# KX1_DB.net
KiCad netlist of a schematic drawn in Altium Designer
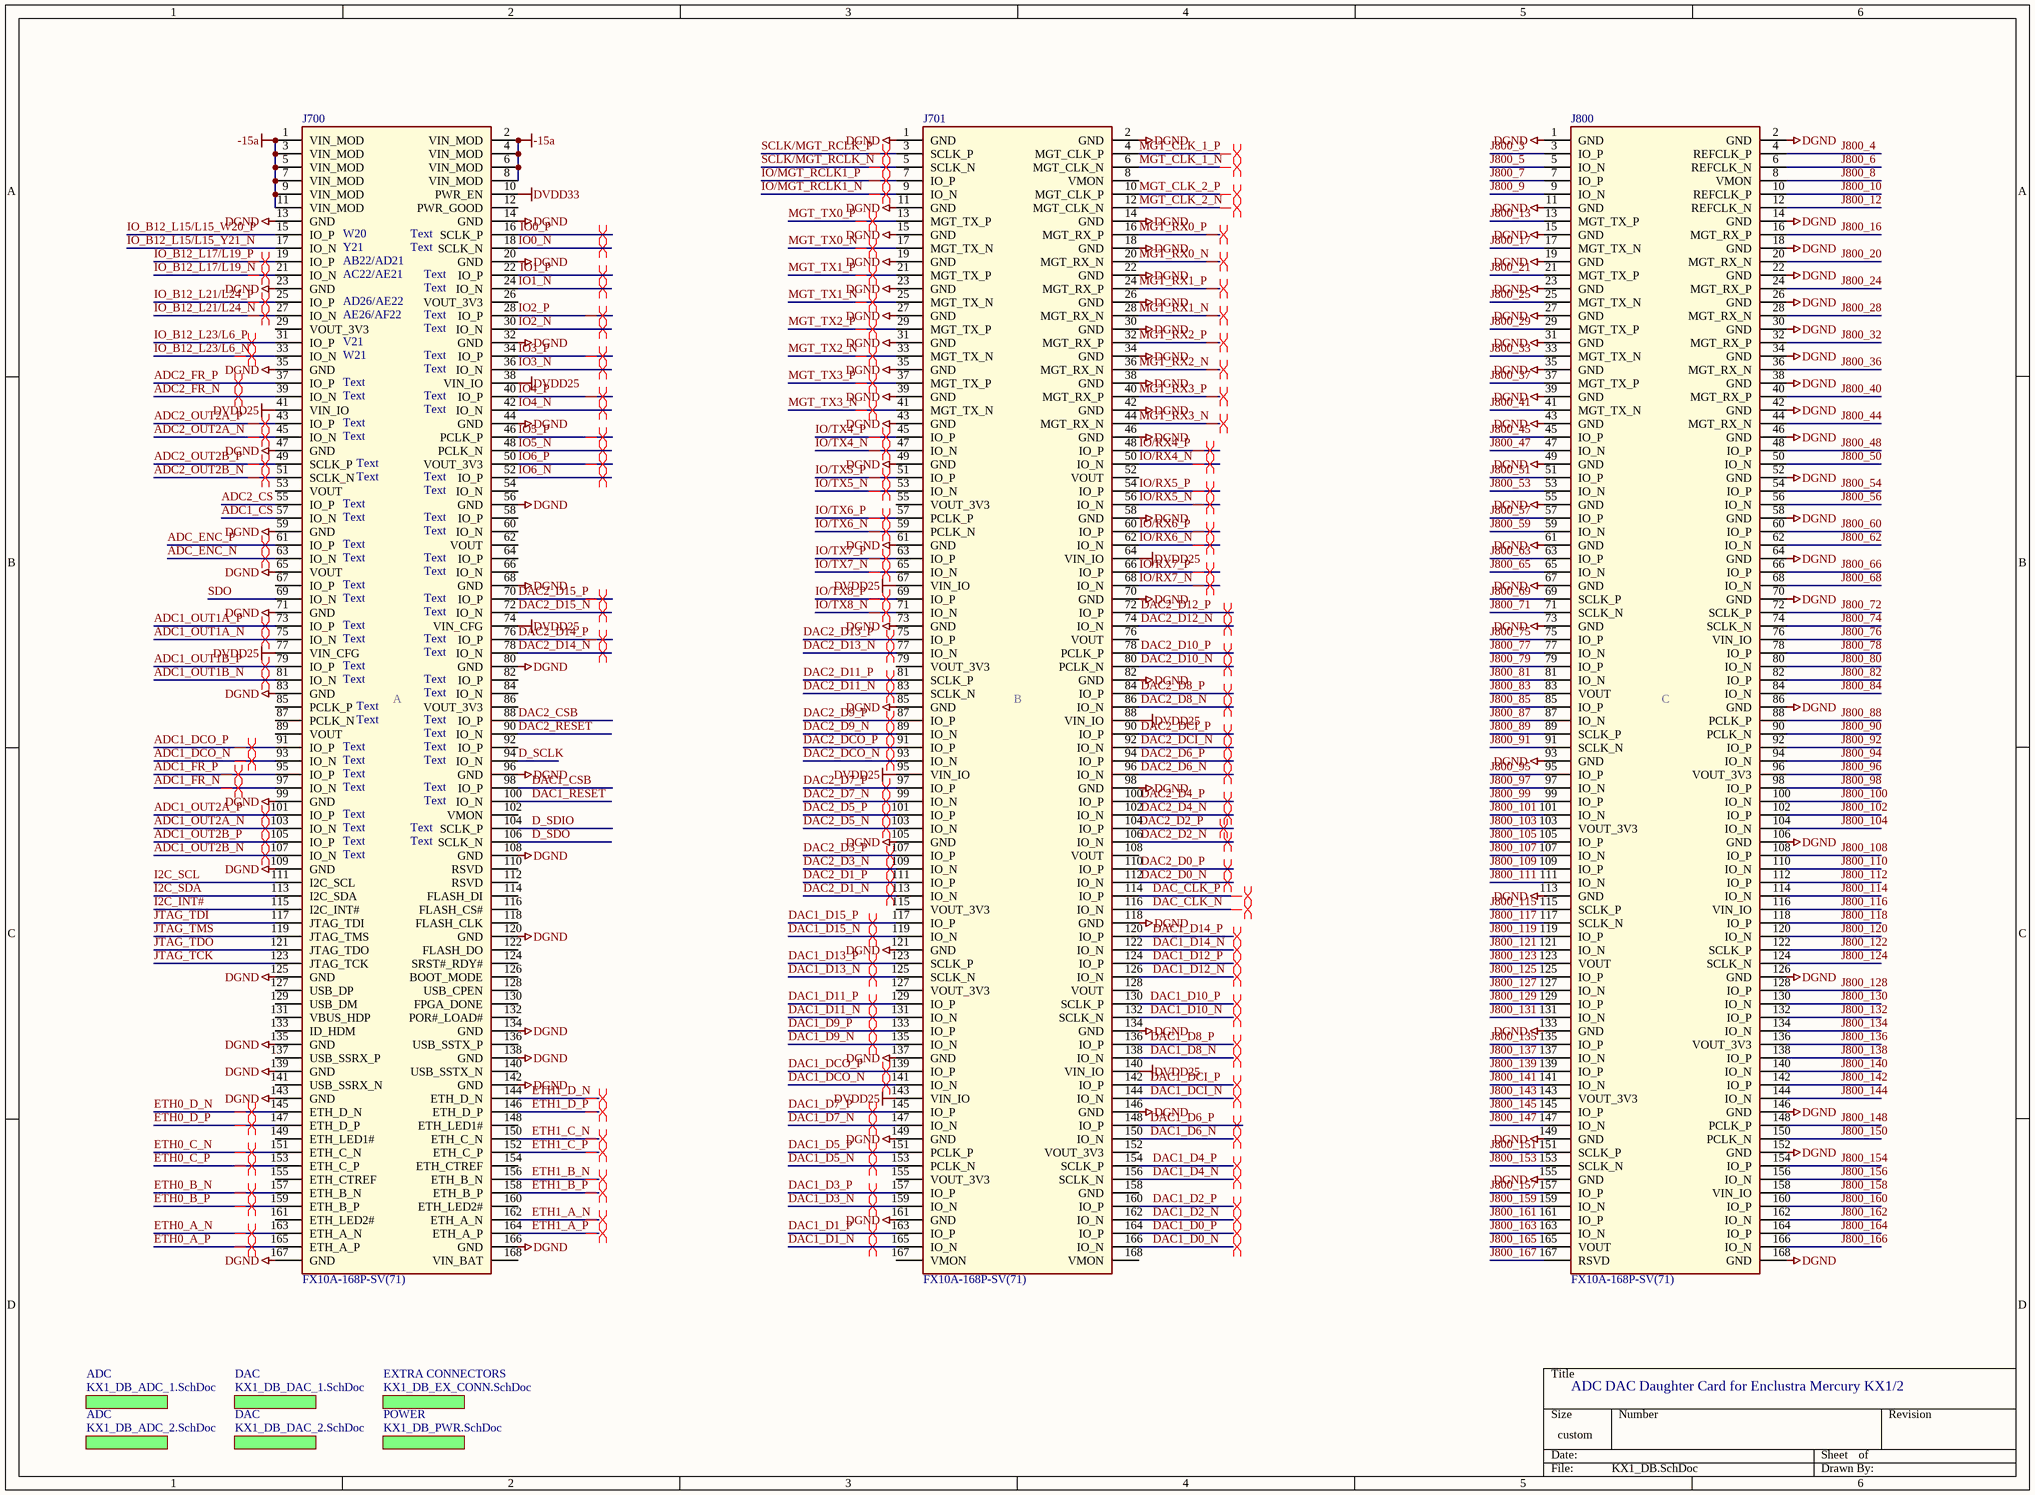
[diagram p0: KX1_DB.SchDoc]

(export (version "E")
  (design (tool "Eeschema 10.0.6"))
  (components
    (comp (ref "J700")
      (value "FX10A-168P-SV(71)")
      (footprint "Mercury_Baseboard_Connector")
      (description "Mercury Baseboard Connector")
      (fields
        (field (name "MANUFACTURER") "Hirose")
        (field (name "DISTPARTNUMBER") "FX10A-168P-SV(71)-ND")
        (field (name "CHECK SCH") "CG_2015-03-03")
      )
      (libsource (lib "Enclustra-Mars-Mercury-Altium-Library") (part "Mercury_Baseboard_Connector-A"))
    )
    (comp (ref "J701")
      (value "FX10A-168P-SV(71)")
      (footprint "Mercury_Baseboard_Connector")
      (description "Mercury Baseboard Connector")
      (fields
        (field (name "MANUFACTURER") "Hirose")
        (field (name "DISTPARTNUMBER") "FX10A-168P-SV(71)-ND")
        (field (name "CHECK SCH") "CG_2015-03-03")
      )
      (libsource (lib "Enclustra-Mars-Mercury-Altium-Library") (part "Mercury_Baseboard_Connector-B"))
    )
    (comp (ref "J800")
      (value "FX10A-168P-SV(71)")
      (footprint "Mercury_Baseboard_Connector")
      (description "Mercury Baseboard Connector")
      (fields
        (field (name "MANUFACTURER") "Hirose")
        (field (name "DISTPARTNUMBER") "FX10A-168P-SV(71)-ND")
        (field (name "CHECK SCH") "CG_2015-03-03")
      )
      (libsource (lib "Enclustra-Mars-Mercury-Altium-Library") (part "Mercury_Baseboard_Connector-C"))
    )
  )
  (nets
    (net (code "1") (name "-15a") (class "Default")
      (node (ref "J700") (pin "1") (pinfunction "VIN_MOD_1") (pintype "power_in"))
      (node (ref "J700") (pin "11") (pinfunction "VIN_MOD_11") (pintype "power_in"))
      (node (ref "J700") (pin "2") (pinfunction "VIN_MOD_2") (pintype "power_in"))
      (node (ref "J700") (pin "3") (pinfunction "VIN_MOD_3") (pintype "power_in"))
      (node (ref "J700") (pin "4") (pinfunction "VIN_MOD_4") (pintype "power_in"))
      (node (ref "J700") (pin "5") (pinfunction "VIN_MOD_5") (pintype "power_in"))
      (node (ref "J700") (pin "6") (pinfunction "VIN_MOD_6") (pintype "power_in"))
      (node (ref "J700") (pin "7") (pinfunction "VIN_MOD_7") (pintype "power_in"))
      (node (ref "J700") (pin "8") (pinfunction "VIN_MOD_8") (pintype "power_in"))
      (node (ref "J700") (pin "9") (pinfunction "VIN_MOD_9") (pintype "power_in"))
    )
    (net (code "2") (name "/ADC1_CS") (class "Default")
      (node (ref "J700") (pin "57") (pinfunction "IO_N_57") (pintype "passive"))
    )
    (net (code "3") (name "/ADC1_DCO_N") (class "Default")
      (node (ref "J700") (pin "93") (pinfunction "IO_N_93") (pintype "passive"))
    )
    (net (code "4") (name "/ADC1_DCO_P") (class "Default")
      (node (ref "J700") (pin "91") (pinfunction "IO_P_91") (pintype "passive"))
    )
    (net (code "5") (name "/ADC1_FR_N") (class "Default")
      (node (ref "J700") (pin "97") (pinfunction "IO_N_97") (pintype "passive"))
    )
    (net (code "6") (name "/ADC1_FR_P") (class "Default")
      (node (ref "J700") (pin "95") (pinfunction "IO_P_95") (pintype "passive"))
    )
    (net (code "7") (name "/ADC1_OUT1A_N") (class "Default")
      (node (ref "J700") (pin "75") (pinfunction "IO_N_75") (pintype "passive"))
    )
    (net (code "8") (name "/ADC1_OUT1A_P") (class "Default")
      (node (ref "J700") (pin "73") (pinfunction "IO_P_73") (pintype "passive"))
    )
    (net (code "9") (name "/ADC1_OUT1B_N") (class "Default")
      (node (ref "J700") (pin "81") (pinfunction "IO_N_81") (pintype "passive"))
    )
    (net (code "10") (name "/ADC1_OUT1B_P") (class "Default")
      (node (ref "J700") (pin "79") (pinfunction "IO_P_79") (pintype "passive"))
    )
    (net (code "11") (name "/ADC1_OUT2A_N") (class "Default")
      (node (ref "J700") (pin "103") (pinfunction "IO_N_103") (pintype "passive"))
    )
    (net (code "12") (name "/ADC1_OUT2A_P") (class "Default")
      (node (ref "J700") (pin "101") (pinfunction "IO_P_101") (pintype "passive"))
    )
    (net (code "13") (name "/ADC1_OUT2B_N") (class "Default")
      (node (ref "J700") (pin "107") (pinfunction "IO_N_107") (pintype "passive"))
    )
    (net (code "14") (name "/ADC1_OUT2B_P") (class "Default")
      (node (ref "J700") (pin "105") (pinfunction "IO_P_105") (pintype "passive"))
    )
    (net (code "15") (name "/ADC2_CS") (class "Default")
      (node (ref "J700") (pin "55") (pinfunction "IO_P_55") (pintype "passive"))
    )
    (net (code "16") (name "/ADC2_FR_N") (class "Default")
      (node (ref "J700") (pin "39") (pinfunction "IO_N_39") (pintype "passive"))
    )
    (net (code "17") (name "/ADC2_FR_P") (class "Default")
      (node (ref "J700") (pin "37") (pinfunction "IO_P_37") (pintype "passive"))
    )
    (net (code "18") (name "/ADC2_OUT2A_N") (class "Default")
      (node (ref "J700") (pin "45") (pinfunction "IO_N_45") (pintype "passive"))
    )
    (net (code "19") (name "/ADC2_OUT2A_P") (class "Default")
      (node (ref "J700") (pin "43") (pinfunction "IO_P_43") (pintype "passive"))
    )
    (net (code "20") (name "/ADC2_OUT2B_N") (class "Default")
      (node (ref "J700") (pin "51") (pinfunction "SCLK_N_51") (pintype "passive"))
    )
    (net (code "21") (name "/ADC2_OUT2B_P") (class "Default")
      (node (ref "J700") (pin "49") (pinfunction "SCLK_P_49") (pintype "passive"))
    )
    (net (code "22") (name "/ADC_ENC_N") (class "Default")
      (node (ref "J700") (pin "63") (pinfunction "IO_N_63") (pintype "passive"))
    )
    (net (code "23") (name "/ADC_ENC_P") (class "Default")
      (node (ref "J700") (pin "61") (pinfunction "IO_P_61") (pintype "passive"))
    )
    (net (code "24") (name "/DAC1_CSB") (class "Default")
      (node (ref "J700") (pin "98") (pinfunction "IO_P_98") (pintype "passive"))
    )
    (net (code "25") (name "/DAC1_D0_N") (class "Default")
      (node (ref "J701") (pin "166") (pinfunction "IO_N_166") (pintype "passive"))
    )
    (net (code "26") (name "/DAC1_D0_P") (class "Default")
      (node (ref "J701") (pin "164") (pinfunction "IO_P_164") (pintype "passive"))
    )
    (net (code "27") (name "/DAC1_D1_N") (class "Default")
      (node (ref "J701") (pin "165") (pinfunction "IO_N_165") (pintype "passive"))
    )
    (net (code "28") (name "/DAC1_D1_P") (class "Default")
      (node (ref "J701") (pin "163") (pinfunction "IO_P_163") (pintype "passive"))
    )
    (net (code "29") (name "/DAC1_D2_N") (class "Default")
      (node (ref "J701") (pin "162") (pinfunction "IO_N_162") (pintype "passive"))
    )
    (net (code "30") (name "/DAC1_D2_P") (class "Default")
      (node (ref "J701") (pin "160") (pinfunction "IO_P_160") (pintype "passive"))
    )
    (net (code "31") (name "/DAC1_D3_N") (class "Default")
      (node (ref "J701") (pin "159") (pinfunction "IO_N_159") (pintype "passive"))
    )
    (net (code "32") (name "/DAC1_D3_P") (class "Default")
      (node (ref "J701") (pin "157") (pinfunction "IO_P_157") (pintype "passive"))
    )
    (net (code "33") (name "/DAC1_D4_N") (class "Default")
      (node (ref "J701") (pin "156") (pinfunction "SCLK_N_156") (pintype "passive"))
    )
    (net (code "34") (name "/DAC1_D4_P") (class "Default")
      (node (ref "J701") (pin "154") (pinfunction "SCLK_P_154") (pintype "passive"))
    )
    (net (code "35") (name "/DAC1_D5_N") (class "Default")
      (node (ref "J701") (pin "153") (pinfunction "PCLK_N_153") (pintype "passive"))
    )
    (net (code "36") (name "/DAC1_D5_P") (class "Default")
      (node (ref "J701") (pin "151") (pinfunction "PCLK_P_151") (pintype "passive"))
    )
    (net (code "37") (name "/DAC1_D6_N") (class "Default")
      (node (ref "J701") (pin "150") (pinfunction "IO_N_150") (pintype "passive"))
    )
    (net (code "38") (name "/DAC1_D6_P") (class "Default")
      (node (ref "J701") (pin "148") (pinfunction "IO_P_148") (pintype "passive"))
    )
    (net (code "39") (name "/DAC1_D7_N") (class "Default")
      (node (ref "J701") (pin "147") (pinfunction "IO_N_147") (pintype "passive"))
    )
    (net (code "40") (name "/DAC1_D7_P") (class "Default")
      (node (ref "J701") (pin "145") (pinfunction "IO_P_145") (pintype "passive"))
    )
    (net (code "41") (name "/DAC1_D8_N") (class "Default")
      (node (ref "J701") (pin "138") (pinfunction "IO_N_138") (pintype "passive"))
    )
    (net (code "42") (name "/DAC1_D8_P") (class "Default")
      (node (ref "J701") (pin "136") (pinfunction "IO_P_136") (pintype "passive"))
    )
    (net (code "43") (name "/DAC1_D9_N") (class "Default")
      (node (ref "J701") (pin "135") (pinfunction "IO_N_135") (pintype "passive"))
    )
    (net (code "44") (name "/DAC1_D9_P") (class "Default")
      (node (ref "J701") (pin "133") (pinfunction "IO_P_133") (pintype "passive"))
    )
    (net (code "45") (name "/DAC1_D10_N") (class "Default")
      (node (ref "J701") (pin "132") (pinfunction "SCLK_N_132") (pintype "passive"))
    )
    (net (code "46") (name "/DAC1_D10_P") (class "Default")
      (node (ref "J701") (pin "130") (pinfunction "SCLK_P_130") (pintype "passive"))
    )
    (net (code "47") (name "/DAC1_D11_N") (class "Default")
      (node (ref "J701") (pin "131") (pinfunction "IO_N_131") (pintype "passive"))
    )
    (net (code "48") (name "/DAC1_D11_P") (class "Default")
      (node (ref "J701") (pin "129") (pinfunction "IO_P_129") (pintype "passive"))
    )
    (net (code "49") (name "/DAC1_D12_N") (class "Default")
      (node (ref "J701") (pin "126") (pinfunction "IO_N_126") (pintype "passive"))
    )
    (net (code "50") (name "/DAC1_D12_P") (class "Default")
      (node (ref "J701") (pin "124") (pinfunction "IO_P_124") (pintype "passive"))
    )
    (net (code "51") (name "/DAC1_D13_N") (class "Default")
      (node (ref "J701") (pin "125") (pinfunction "SCLK_N_125") (pintype "passive"))
    )
    (net (code "52") (name "/DAC1_D13_P") (class "Default")
      (node (ref "J701") (pin "123") (pinfunction "SCLK_P_123") (pintype "passive"))
    )
    (net (code "53") (name "/DAC1_D14_N") (class "Default")
      (node (ref "J701") (pin "122") (pinfunction "IO_N_122") (pintype "passive"))
    )
    (net (code "54") (name "/DAC1_D14_P") (class "Default")
      (node (ref "J701") (pin "120") (pinfunction "IO_P_120") (pintype "passive"))
    )
    (net (code "55") (name "/DAC1_D15_N") (class "Default")
      (node (ref "J701") (pin "119") (pinfunction "IO_N_119") (pintype "passive"))
    )
    (net (code "56") (name "/DAC1_D15_P") (class "Default")
      (node (ref "J701") (pin "117") (pinfunction "IO_P_117") (pintype "passive"))
    )
    (net (code "57") (name "/DAC1_DCI_N") (class "Default")
      (node (ref "J701") (pin "144") (pinfunction "IO_N_144") (pintype "passive"))
    )
    (net (code "58") (name "/DAC1_DCI_P") (class "Default")
      (node (ref "J701") (pin "142") (pinfunction "IO_P_142") (pintype "passive"))
    )
    (net (code "59") (name "/DAC1_DCO_N") (class "Default")
      (node (ref "J701") (pin "141") (pinfunction "IO_N_141") (pintype "passive"))
    )
    (net (code "60") (name "/DAC1_DCO_P") (class "Default")
      (node (ref "J701") (pin "139") (pinfunction "IO_P_139") (pintype "passive"))
    )
    (net (code "61") (name "/DAC1_RESET") (class "Default")
      (node (ref "J700") (pin "100") (pinfunction "IO_N_100") (pintype "passive"))
    )
    (net (code "62") (name "/DAC2_CSB") (class "Default")
      (node (ref "J700") (pin "88") (pinfunction "IO_P_88") (pintype "passive"))
    )
    (net (code "63") (name "/DAC2_D0_N") (class "Default")
      (node (ref "J701") (pin "112") (pinfunction "IO_N_112") (pintype "passive"))
    )
    (net (code "64") (name "/DAC2_D0_P") (class "Default")
      (node (ref "J701") (pin "110") (pinfunction "IO_P_110") (pintype "passive"))
    )
    (net (code "65") (name "/DAC2_D1_N") (class "Default")
      (node (ref "J701") (pin "113") (pinfunction "IO_N_113") (pintype "passive"))
    )
    (net (code "66") (name "/DAC2_D1_P") (class "Default")
      (node (ref "J701") (pin "111") (pinfunction "IO_P_111") (pintype "passive"))
    )
    (net (code "67") (name "/DAC2_D2_N") (class "Default")
      (node (ref "J701") (pin "106") (pinfunction "IO_N_106") (pintype "passive"))
    )
    (net (code "68") (name "/DAC2_D2_P") (class "Default")
      (node (ref "J701") (pin "104") (pinfunction "IO_P_104") (pintype "passive"))
    )
    (net (code "69") (name "/DAC2_D3_N") (class "Default")
      (node (ref "J701") (pin "109") (pinfunction "IO_N_109") (pintype "passive"))
    )
    (net (code "70") (name "/DAC2_D3_P") (class "Default")
      (node (ref "J701") (pin "107") (pinfunction "IO_P_107") (pintype "passive"))
    )
    (net (code "71") (name "/DAC2_D4_N") (class "Default")
      (node (ref "J701") (pin "102") (pinfunction "IO_N_102") (pintype "passive"))
    )
    (net (code "72") (name "/DAC2_D4_P") (class "Default")
      (node (ref "J701") (pin "100") (pinfunction "IO_P_100") (pintype "passive"))
    )
    (net (code "73") (name "/DAC2_D5_N") (class "Default")
      (node (ref "J701") (pin "103") (pinfunction "IO_N_103") (pintype "passive"))
    )
    (net (code "74") (name "/DAC2_D5_P") (class "Default")
      (node (ref "J701") (pin "101") (pinfunction "IO_P_101") (pintype "passive"))
    )
    (net (code "75") (name "/DAC2_D6_N") (class "Default")
      (node (ref "J701") (pin "96") (pinfunction "IO_N_96") (pintype "passive"))
    )
    (net (code "76") (name "/DAC2_D6_P") (class "Default")
      (node (ref "J701") (pin "94") (pinfunction "IO_P_94") (pintype "passive"))
    )
    (net (code "77") (name "/DAC2_D7_N") (class "Default")
      (node (ref "J701") (pin "99") (pinfunction "IO_N_99") (pintype "passive"))
    )
    (net (code "78") (name "/DAC2_D7_P") (class "Default")
      (node (ref "J701") (pin "97") (pinfunction "IO_P_97") (pintype "passive"))
    )
    (net (code "79") (name "/DAC2_D8_N") (class "Default")
      (node (ref "J701") (pin "86") (pinfunction "IO_N_86") (pintype "passive"))
    )
    (net (code "80") (name "/DAC2_D8_P") (class "Default")
      (node (ref "J701") (pin "84") (pinfunction "IO_P_84") (pintype "passive"))
    )
    (net (code "81") (name "/DAC2_D9_N") (class "Default")
      (node (ref "J701") (pin "89") (pinfunction "IO_N_89") (pintype "passive"))
    )
    (net (code "82") (name "/DAC2_D9_P") (class "Default")
      (node (ref "J701") (pin "87") (pinfunction "IO_P_87") (pintype "passive"))
    )
    (net (code "83") (name "/DAC2_D10_N") (class "Default")
      (node (ref "J701") (pin "80") (pinfunction "PCLK_N_80") (pintype "passive"))
    )
    (net (code "84") (name "/DAC2_D10_P") (class "Default")
      (node (ref "J701") (pin "78") (pinfunction "PCLK_P_78") (pintype "passive"))
    )
    (net (code "85") (name "/DAC2_D11_N") (class "Default")
      (node (ref "J701") (pin "83") (pinfunction "SCLK_N_83") (pintype "passive"))
    )
    (net (code "86") (name "/DAC2_D11_P") (class "Default")
      (node (ref "J701") (pin "81") (pinfunction "SCLK_P_81") (pintype "passive"))
    )
    (net (code "87") (name "/DAC2_D12_N") (class "Default")
      (node (ref "J701") (pin "74") (pinfunction "IO_N_74") (pintype "passive"))
    )
    (net (code "88") (name "/DAC2_D12_P") (class "Default")
      (node (ref "J701") (pin "72") (pinfunction "IO_P_72") (pintype "passive"))
    )
    (net (code "89") (name "/DAC2_D13_N") (class "Default")
      (node (ref "J701") (pin "77") (pinfunction "IO_N_77") (pintype "passive"))
    )
    (net (code "90") (name "/DAC2_D13_P") (class "Default")
      (node (ref "J701") (pin "75") (pinfunction "IO_P_75") (pintype "passive"))
    )
    (net (code "91") (name "/DAC2_D14_N") (class "Default")
      (node (ref "J700") (pin "78") (pinfunction "IO_N_78") (pintype "passive"))
    )
    (net (code "92") (name "/DAC2_D14_P") (class "Default")
      (node (ref "J700") (pin "76") (pinfunction "IO_P_76") (pintype "passive"))
    )
    (net (code "93") (name "/DAC2_D15_N") (class "Default")
      (node (ref "J700") (pin "72") (pinfunction "IO_N_72") (pintype "passive"))
    )
    (net (code "94") (name "/DAC2_D15_P") (class "Default")
      (node (ref "J700") (pin "70") (pinfunction "IO_P_70") (pintype "passive"))
    )
    (net (code "95") (name "/DAC2_DCI_N") (class "Default")
      (node (ref "J701") (pin "92") (pinfunction "IO_N_92") (pintype "passive"))
    )
    (net (code "96") (name "/DAC2_DCI_P") (class "Default")
      (node (ref "J701") (pin "90") (pinfunction "IO_P_90") (pintype "passive"))
    )
    (net (code "97") (name "/DAC2_DCO_N") (class "Default")
      (node (ref "J701") (pin "93") (pinfunction "IO_N_93") (pintype "passive"))
    )
    (net (code "98") (name "/DAC2_DCO_P") (class "Default")
      (node (ref "J701") (pin "91") (pinfunction "IO_P_91") (pintype "passive"))
    )
    (net (code "99") (name "/DAC2_RESET") (class "Default")
      (node (ref "J700") (pin "90") (pinfunction "IO_N_90") (pintype "passive"))
    )
    (net (code "100") (name "/DAC_CLK_N") (class "Default")
      (node (ref "J701") (pin "116") (pinfunction "IO_N_116") (pintype "passive"))
    )
    (net (code "101") (name "/DAC_CLK_P") (class "Default")
      (node (ref "J701") (pin "114") (pinfunction "IO_P_114") (pintype "passive"))
    )
    (net (code "102") (name "/D_SCLK") (class "Default")
      (node (ref "J700") (pin "94") (pinfunction "IO_N_94") (pintype "passive"))
    )
    (net (code "103") (name "/D_SDIO") (class "Default")
      (node (ref "J700") (pin "104") (pinfunction "SCLK_P_104") (pintype "passive"))
    )
    (net (code "104") (name "/D_SDO") (class "Default")
      (node (ref "J700") (pin "106") (pinfunction "SCLK_N_106") (pintype "passive"))
    )
    (net (code "105") (name "/ETH0_A_N") (class "Default")
      (node (ref "J700") (pin "163") (pinfunction "ETH_A_N_163") (pintype "passive"))
    )
    (net (code "106") (name "/ETH0_A_P") (class "Default")
      (node (ref "J700") (pin "165") (pinfunction "ETH_A_P_165") (pintype "passive"))
    )
    (net (code "107") (name "/ETH0_B_N") (class "Default")
      (node (ref "J700") (pin "157") (pinfunction "ETH_B_N_157") (pintype "passive"))
    )
    (net (code "108") (name "/ETH0_B_P") (class "Default")
      (node (ref "J700") (pin "159") (pinfunction "ETH_B_P_159") (pintype "passive"))
    )
    (net (code "109") (name "/ETH0_C_N") (class "Default")
      (node (ref "J700") (pin "151") (pinfunction "ETH_C_N_151") (pintype "passive"))
    )
    (net (code "110") (name "/ETH0_C_P") (class "Default")
      (node (ref "J700") (pin "153") (pinfunction "ETH_C_P_153") (pintype "passive"))
    )
    (net (code "111") (name "/ETH0_D_N") (class "Default")
      (node (ref "J700") (pin "145") (pinfunction "ETH_D_N_145") (pintype "passive"))
    )
    (net (code "112") (name "/ETH0_D_P") (class "Default")
      (node (ref "J700") (pin "147") (pinfunction "ETH_D_P_147") (pintype "passive"))
    )
    (net (code "113") (name "/ETH1_A_N") (class "Default")
      (node (ref "J700") (pin "162") (pinfunction "ETH_A_N_162") (pintype "passive"))
    )
    (net (code "114") (name "/ETH1_A_P") (class "Default")
      (node (ref "J700") (pin "164") (pinfunction "ETH_A_P_164") (pintype "passive"))
    )
    (net (code "115") (name "/ETH1_B_N") (class "Default")
      (node (ref "J700") (pin "156") (pinfunction "ETH_B_N_156") (pintype "passive"))
    )
    (net (code "116") (name "/ETH1_B_P") (class "Default")
      (node (ref "J700") (pin "158") (pinfunction "ETH_B_P_158") (pintype "passive"))
    )
    (net (code "117") (name "/ETH1_C_N") (class "Default")
      (node (ref "J700") (pin "150") (pinfunction "ETH_C_N_150") (pintype "passive"))
    )
    (net (code "118") (name "/ETH1_C_P") (class "Default")
      (node (ref "J700") (pin "152") (pinfunction "ETH_C_P_152") (pintype "passive"))
    )
    (net (code "119") (name "/ETH1_D_N") (class "Default")
      (node (ref "J700") (pin "144") (pinfunction "ETH_D_N_144") (pintype "passive"))
    )
    (net (code "120") (name "/ETH1_D_P") (class "Default")
      (node (ref "J700") (pin "146") (pinfunction "ETH_D_P_146") (pintype "passive"))
    )
    (net (code "121") (name "/I2C_INT#") (class "Default")
      (node (ref "J700") (pin "115") (pinfunction "I2C_INT#_115") (pintype "passive"))
    )
    (net (code "122") (name "/I2C_SCL") (class "Default")
      (node (ref "J700") (pin "111") (pinfunction "I2C_SCL_111") (pintype "passive"))
    )
    (net (code "123") (name "/I2C_SDA") (class "Default")
      (node (ref "J700") (pin "113") (pinfunction "I2C_SDA_113") (pintype "passive"))
    )
    (net (code "124") (name "/IO0_N") (class "Default")
      (node (ref "J700") (pin "18") (pinfunction "SCLK_N_18") (pintype "passive"))
    )
    (net (code "125") (name "/IO0_P") (class "Default")
      (node (ref "J700") (pin "16") (pinfunction "SCLK_P_16") (pintype "passive"))
    )
    (net (code "126") (name "/IO1_N") (class "Default")
      (node (ref "J700") (pin "24") (pinfunction "IO_N_24") (pintype "passive"))
    )
    (net (code "127") (name "/IO1_P") (class "Default")
      (node (ref "J700") (pin "22") (pinfunction "IO_P_22") (pintype "passive"))
    )
    (net (code "128") (name "/IO2_N") (class "Default")
      (node (ref "J700") (pin "30") (pinfunction "IO_N_30") (pintype "passive"))
    )
    (net (code "129") (name "/IO2_P") (class "Default")
      (node (ref "J700") (pin "28") (pinfunction "IO_P_28") (pintype "passive"))
    )
    (net (code "130") (name "/IO3_N") (class "Default")
      (node (ref "J700") (pin "36") (pinfunction "IO_N_36") (pintype "passive"))
    )
    (net (code "131") (name "/IO3_P") (class "Default")
      (node (ref "J700") (pin "34") (pinfunction "IO_P_34") (pintype "passive"))
    )
    (net (code "132") (name "/IO4_N") (class "Default")
      (node (ref "J700") (pin "42") (pinfunction "IO_N_42") (pintype "passive"))
    )
    (net (code "133") (name "/IO4_P") (class "Default")
      (node (ref "J700") (pin "40") (pinfunction "IO_P_40") (pintype "passive"))
    )
    (net (code "134") (name "/IO5_N") (class "Default")
      (node (ref "J700") (pin "48") (pinfunction "PCLK_N_48") (pintype "passive"))
    )
    (net (code "135") (name "/IO5_P") (class "Default")
      (node (ref "J700") (pin "46") (pinfunction "PCLK_P_46") (pintype "passive"))
    )
    (net (code "136") (name "/IO6_N") (class "Default")
      (node (ref "J700") (pin "52") (pinfunction "IO_P_52") (pintype "passive"))
    )
    (net (code "137") (name "/IO6_P") (class "Default")
      (node (ref "J700") (pin "50") (pinfunction "VOUT_3V3_50") (pintype "power_in"))
    )
    (net (code "138") (name "/IO_B12_L15{slash}L15_W20_P") (class "Default")
      (node (ref "J700") (pin "15") (pinfunction "IO_P_15") (pintype "passive"))
    )
    (net (code "139") (name "/IO_B12_L15{slash}L15_Y21_N") (class "Default")
      (node (ref "J700") (pin "17") (pinfunction "IO_N_17") (pintype "passive"))
    )
    (net (code "140") (name "/IO_B12_L17{slash}L19_N") (class "Default")
      (node (ref "J700") (pin "21") (pinfunction "IO_N_21") (pintype "passive"))
    )
    (net (code "141") (name "/IO_B12_L17{slash}L19_P") (class "Default")
      (node (ref "J700") (pin "19") (pinfunction "IO_P_19") (pintype "passive"))
    )
    (net (code "142") (name "/IO_B12_L21{slash}L24_N") (class "Default")
      (node (ref "J700") (pin "27") (pinfunction "IO_N_27") (pintype "passive"))
    )
    (net (code "143") (name "/IO_B12_L21{slash}L24_P") (class "Default")
      (node (ref "J700") (pin "25") (pinfunction "IO_P_25") (pintype "passive"))
    )
    (net (code "144") (name "/IO_B12_L23{slash}L6_N") (class "Default")
      (node (ref "J700") (pin "33") (pinfunction "IO_N_33") (pintype "passive"))
    )
    (net (code "145") (name "/IO_B12_L23{slash}L6_P") (class "Default")
      (node (ref "J700") (pin "31") (pinfunction "IO_P_31") (pintype "passive"))
    )
    (net (code "146") (name "/IO{slash}MGT_RCLK1_N") (class "Default")
      (node (ref "J701") (pin "9") (pinfunction "IO_N_9") (pintype "passive"))
    )
    (net (code "147") (name "/IO{slash}MGT_RCLK1_P") (class "Default")
      (node (ref "J701") (pin "7") (pinfunction "IO_P_7") (pintype "passive"))
    )
    (net (code "148") (name "/IO{slash}RX4_N") (class "Default")
      (node (ref "J701") (pin "50") (pinfunction "IO_N_50") (pintype "passive"))
    )
    (net (code "149") (name "/IO{slash}RX4_P") (class "Default")
      (node (ref "J701") (pin "48") (pinfunction "IO_P_48") (pintype "passive"))
    )
    (net (code "150") (name "/IO{slash}RX5_N") (class "Default")
      (node (ref "J701") (pin "56") (pinfunction "IO_N_56") (pintype "passive"))
    )
    (net (code "151") (name "/IO{slash}RX5_P") (class "Default")
      (node (ref "J701") (pin "54") (pinfunction "IO_P_54") (pintype "passive"))
    )
    (net (code "152") (name "/IO{slash}RX6_N") (class "Default")
      (node (ref "J701") (pin "62") (pinfunction "IO_N_62") (pintype "passive"))
    )
    (net (code "153") (name "/IO{slash}RX6_P") (class "Default")
      (node (ref "J701") (pin "60") (pinfunction "IO_P_60") (pintype "passive"))
    )
    (net (code "154") (name "/IO{slash}RX7_N") (class "Default")
      (node (ref "J701") (pin "68") (pinfunction "IO_N_68") (pintype "passive"))
    )
    (net (code "155") (name "/IO{slash}RX7_P") (class "Default")
      (node (ref "J701") (pin "66") (pinfunction "IO_P_66") (pintype "passive"))
    )
    (net (code "156") (name "/IO{slash}TX4_N") (class "Default")
      (node (ref "J701") (pin "47") (pinfunction "IO_N_47") (pintype "passive"))
    )
    (net (code "157") (name "/IO{slash}TX4_P") (class "Default")
      (node (ref "J701") (pin "45") (pinfunction "IO_P_45") (pintype "passive"))
    )
    (net (code "158") (name "/IO{slash}TX5_N") (class "Default")
      (node (ref "J701") (pin "53") (pinfunction "IO_N_53") (pintype "passive"))
    )
    (net (code "159") (name "/IO{slash}TX5_P") (class "Default")
      (node (ref "J701") (pin "51") (pinfunction "IO_P_51") (pintype "passive"))
    )
    (net (code "160") (name "/IO{slash}TX6_N") (class "Default")
      (node (ref "J701") (pin "59") (pinfunction "PCLK_N_59") (pintype "passive"))
    )
    (net (code "161") (name "/IO{slash}TX6_P") (class "Default")
      (node (ref "J701") (pin "57") (pinfunction "PCLK_P_57") (pintype "passive"))
    )
    (net (code "162") (name "/IO{slash}TX7_N") (class "Default")
      (node (ref "J701") (pin "65") (pinfunction "IO_N_65") (pintype "passive"))
    )
    (net (code "163") (name "/IO{slash}TX7_P") (class "Default")
      (node (ref "J701") (pin "63") (pinfunction "IO_P_63") (pintype "passive"))
    )
    (net (code "164") (name "/IO{slash}TX8_N") (class "Default")
      (node (ref "J701") (pin "71") (pinfunction "IO_N_71") (pintype "passive"))
    )
    (net (code "165") (name "/IO{slash}TX8_P") (class "Default")
      (node (ref "J701") (pin "69") (pinfunction "IO_P_69") (pintype "passive"))
    )
    (net (code "166") (name "/J800_3") (class "Default")
      (node (ref "J800") (pin "3") (pinfunction "IO_P_3") (pintype "passive"))
    )
    (net (code "167") (name "/J800_4") (class "Default")
      (node (ref "J800") (pin "4") (pinfunction "REFCLK_P_4") (pintype "passive"))
    )
    (net (code "168") (name "/J800_5") (class "Default")
      (node (ref "J800") (pin "5") (pinfunction "IO_N_5") (pintype "passive"))
    )
    (net (code "169") (name "/J800_6") (class "Default")
      (node (ref "J800") (pin "6") (pinfunction "REFCLK_N_6") (pintype "passive"))
    )
    (net (code "170") (name "/J800_7") (class "Default")
      (node (ref "J800") (pin "7") (pinfunction "IO_P_7") (pintype "passive"))
    )
    (net (code "171") (name "/J800_8") (class "Default")
      (node (ref "J800") (pin "8") (pinfunction "VMON_8") (pintype "passive"))
    )
    (net (code "172") (name "/J800_9") (class "Default")
      (node (ref "J800") (pin "9") (pinfunction "IO_N_9") (pintype "passive"))
    )
    (net (code "173") (name "/J800_10") (class "Default")
      (node (ref "J800") (pin "10") (pinfunction "REFCLK_P_10") (pintype "passive"))
    )
    (net (code "174") (name "/J800_12") (class "Default")
      (node (ref "J800") (pin "12") (pinfunction "REFCLK_N_12") (pintype "passive"))
    )
    (net (code "175") (name "/J800_13") (class "Default")
      (node (ref "J800") (pin "13") (pinfunction "MGT_TX_P_13") (pintype "passive"))
    )
    (net (code "176") (name "/J800_16") (class "Default")
      (node (ref "J800") (pin "16") (pinfunction "MGT_RX_P_16") (pintype "passive"))
    )
    (net (code "177") (name "/J800_17") (class "Default")
      (node (ref "J800") (pin "17") (pinfunction "MGT_TX_N_17") (pintype "passive"))
    )
    (net (code "178") (name "/J800_20") (class "Default")
      (node (ref "J800") (pin "20") (pinfunction "MGT_RX_N_20") (pintype "passive"))
    )
    (net (code "179") (name "/J800_21") (class "Default")
      (node (ref "J800") (pin "21") (pinfunction "MGT_TX_P_21") (pintype "passive"))
    )
    (net (code "180") (name "/J800_24") (class "Default")
      (node (ref "J800") (pin "24") (pinfunction "MGT_RX_P_24") (pintype "passive"))
    )
    (net (code "181") (name "/J800_25") (class "Default")
      (node (ref "J800") (pin "25") (pinfunction "MGT_TX_N_25") (pintype "passive"))
    )
    (net (code "182") (name "/J800_28") (class "Default")
      (node (ref "J800") (pin "28") (pinfunction "MGT_RX_N_28") (pintype "passive"))
    )
    (net (code "183") (name "/J800_29") (class "Default")
      (node (ref "J800") (pin "29") (pinfunction "MGT_TX_P_29") (pintype "passive"))
    )
    (net (code "184") (name "/J800_32") (class "Default")
      (node (ref "J800") (pin "32") (pinfunction "MGT_RX_P_32") (pintype "passive"))
    )
    (net (code "185") (name "/J800_33") (class "Default")
      (node (ref "J800") (pin "33") (pinfunction "MGT_TX_N_33") (pintype "passive"))
    )
    (net (code "186") (name "/J800_36") (class "Default")
      (node (ref "J800") (pin "36") (pinfunction "MGT_RX_N_36") (pintype "passive"))
    )
    (net (code "187") (name "/J800_37") (class "Default")
      (node (ref "J800") (pin "37") (pinfunction "MGT_TX_P_37") (pintype "passive"))
    )
    (net (code "188") (name "/J800_40") (class "Default")
      (node (ref "J800") (pin "40") (pinfunction "MGT_RX_P_40") (pintype "passive"))
    )
    (net (code "189") (name "/J800_41") (class "Default")
      (node (ref "J800") (pin "41") (pinfunction "MGT_TX_N_41") (pintype "passive"))
    )
    (net (code "190") (name "/J800_44") (class "Default")
      (node (ref "J800") (pin "44") (pinfunction "MGT_RX_N_44") (pintype "passive"))
    )
    (net (code "191") (name "/J800_45") (class "Default")
      (node (ref "J800") (pin "45") (pinfunction "IO_P_45") (pintype "passive"))
    )
    (net (code "192") (name "/J800_47") (class "Default")
      (node (ref "J800") (pin "47") (pinfunction "IO_N_47") (pintype "passive"))
    )
    (net (code "193") (name "/J800_48") (class "Default")
      (node (ref "J800") (pin "48") (pinfunction "IO_P_48") (pintype "passive"))
    )
    (net (code "194") (name "/J800_50") (class "Default")
      (node (ref "J800") (pin "50") (pinfunction "IO_N_50") (pintype "passive"))
    )
    (net (code "195") (name "/J800_51") (class "Default")
      (node (ref "J800") (pin "51") (pinfunction "IO_P_51") (pintype "passive"))
    )
    (net (code "196") (name "/J800_53") (class "Default")
      (node (ref "J800") (pin "53") (pinfunction "IO_N_53") (pintype "passive"))
    )
    (net (code "197") (name "/J800_54") (class "Default")
      (node (ref "J800") (pin "54") (pinfunction "IO_P_54") (pintype "passive"))
    )
    (net (code "198") (name "/J800_56") (class "Default")
      (node (ref "J800") (pin "56") (pinfunction "IO_N_56") (pintype "passive"))
    )
    (net (code "199") (name "/J800_57") (class "Default")
      (node (ref "J800") (pin "57") (pinfunction "IO_P_57") (pintype "passive"))
    )
    (net (code "200") (name "/J800_59") (class "Default")
      (node (ref "J800") (pin "59") (pinfunction "IO_N_59") (pintype "passive"))
    )
    (net (code "201") (name "/J800_60") (class "Default")
      (node (ref "J800") (pin "60") (pinfunction "IO_P_60") (pintype "passive"))
    )
    (net (code "202") (name "/J800_62") (class "Default")
      (node (ref "J800") (pin "62") (pinfunction "IO_N_62") (pintype "passive"))
    )
    (net (code "203") (name "/J800_63") (class "Default")
      (node (ref "J800") (pin "63") (pinfunction "IO_P_63") (pintype "passive"))
    )
    (net (code "204") (name "/J800_65") (class "Default")
      (node (ref "J800") (pin "65") (pinfunction "IO_N_65") (pintype "passive"))
    )
    (net (code "205") (name "/J800_66") (class "Default")
      (node (ref "J800") (pin "66") (pinfunction "IO_P_66") (pintype "passive"))
    )
    (net (code "206") (name "/J800_68") (class "Default")
      (node (ref "J800") (pin "68") (pinfunction "IO_N_68") (pintype "passive"))
    )
    (net (code "207") (name "/J800_69") (class "Default")
      (node (ref "J800") (pin "69") (pinfunction "SCLK_P_69") (pintype "passive"))
    )
    (net (code "208") (name "/J800_71") (class "Default")
      (node (ref "J800") (pin "71") (pinfunction "SCLK_N_71") (pintype "passive"))
    )
    (net (code "209") (name "/J800_72") (class "Default")
      (node (ref "J800") (pin "72") (pinfunction "SCLK_P_72") (pintype "passive"))
    )
    (net (code "210") (name "/J800_74") (class "Default")
      (node (ref "J800") (pin "74") (pinfunction "SCLK_N_74") (pintype "passive"))
    )
    (net (code "211") (name "/J800_75") (class "Default")
      (node (ref "J800") (pin "75") (pinfunction "IO_P_75") (pintype "passive"))
    )
    (net (code "212") (name "/J800_76") (class "Default")
      (node (ref "J800") (pin "76") (pinfunction "VIN_IO_76") (pintype "passive"))
    )
    (net (code "213") (name "/J800_77") (class "Default")
      (node (ref "J800") (pin "77") (pinfunction "IO_N_77") (pintype "passive"))
    )
    (net (code "214") (name "/J800_78") (class "Default")
      (node (ref "J800") (pin "78") (pinfunction "IO_P_78") (pintype "passive"))
    )
    (net (code "215") (name "/J800_79") (class "Default")
      (node (ref "J800") (pin "79") (pinfunction "IO_P_79") (pintype "passive"))
    )
    (net (code "216") (name "/J800_80") (class "Default")
      (node (ref "J800") (pin "80") (pinfunction "IO_N_80") (pintype "passive"))
    )
    (net (code "217") (name "/J800_81") (class "Default")
      (node (ref "J800") (pin "81") (pinfunction "IO_N_81") (pintype "passive"))
    )
    (net (code "218") (name "/J800_82") (class "Default")
      (node (ref "J800") (pin "82") (pinfunction "IO_P_82") (pintype "passive"))
    )
    (net (code "219") (name "/J800_83") (class "Default")
      (node (ref "J800") (pin "83") (pinfunction "VOUT_83") (pintype "passive"))
    )
    (net (code "220") (name "/J800_84") (class "Default")
      (node (ref "J800") (pin "84") (pinfunction "IO_N_84") (pintype "passive"))
    )
    (net (code "221") (name "/J800_85") (class "Default")
      (node (ref "J800") (pin "85") (pinfunction "IO_P_85") (pintype "passive"))
    )
    (net (code "222") (name "/J800_87") (class "Default")
      (node (ref "J800") (pin "87") (pinfunction "IO_N_87") (pintype "passive"))
    )
    (net (code "223") (name "/J800_88") (class "Default")
      (node (ref "J800") (pin "88") (pinfunction "PCLK_P_88") (pintype "passive"))
    )
    (net (code "224") (name "/J800_89") (class "Default")
      (node (ref "J800") (pin "89") (pinfunction "SCLK_P_89") (pintype "passive"))
    )
    (net (code "225") (name "/J800_90") (class "Default")
      (node (ref "J800") (pin "90") (pinfunction "PCLK_N_90") (pintype "passive"))
    )
    (net (code "226") (name "/J800_91") (class "Default")
      (node (ref "J800") (pin "91") (pinfunction "SCLK_N_91") (pintype "passive"))
    )
    (net (code "227") (name "/J800_92") (class "Default")
      (node (ref "J800") (pin "92") (pinfunction "IO_P_92") (pintype "passive"))
    )
    (net (code "228") (name "/J800_94") (class "Default")
      (node (ref "J800") (pin "94") (pinfunction "IO_N_94") (pintype "passive"))
    )
    (net (code "229") (name "/J800_95") (class "Default")
      (node (ref "J800") (pin "95") (pinfunction "IO_P_95") (pintype "passive"))
    )
    (net (code "230") (name "/J800_96") (class "Default")
      (node (ref "J800") (pin "96") (pinfunction "VOUT_3V3_96") (pintype "passive"))
    )
    (net (code "231") (name "/J800_97") (class "Default")
      (node (ref "J800") (pin "97") (pinfunction "IO_N_97") (pintype "passive"))
    )
    (net (code "232") (name "/J800_98") (class "Default")
      (node (ref "J800") (pin "98") (pinfunction "IO_P_98") (pintype "passive"))
    )
    (net (code "233") (name "/J800_99") (class "Default")
      (node (ref "J800") (pin "99") (pinfunction "IO_P_99") (pintype "passive"))
    )
    (net (code "234") (name "/J800_100") (class "Default")
      (node (ref "J800") (pin "100") (pinfunction "IO_N_100") (pintype "passive"))
    )
    (net (code "235") (name "/J800_101") (class "Default")
      (node (ref "J800") (pin "101") (pinfunction "IO_N_101") (pintype "passive"))
    )
    (net (code "236") (name "/J800_102") (class "Default")
      (node (ref "J800") (pin "102") (pinfunction "IO_P_102") (pintype "passive"))
    )
    (net (code "237") (name "/J800_103") (class "Default")
      (node (ref "J800") (pin "103") (pinfunction "VOUT_3V3_103") (pintype "passive"))
    )
    (net (code "238") (name "/J800_104") (class "Default")
      (node (ref "J800") (pin "104") (pinfunction "IO_N_104") (pintype "passive"))
    )
    (net (code "239") (name "/J800_105") (class "Default")
      (node (ref "J800") (pin "105") (pinfunction "IO_P_105") (pintype "passive"))
    )
    (net (code "240") (name "/J800_107") (class "Default")
      (node (ref "J800") (pin "107") (pinfunction "IO_N_107") (pintype "passive"))
    )
    (net (code "241") (name "/J800_108") (class "Default")
      (node (ref "J800") (pin "108") (pinfunction "IO_P_108") (pintype "passive"))
    )
    (net (code "242") (name "/J800_109") (class "Default")
      (node (ref "J800") (pin "109") (pinfunction "IO_P_109") (pintype "passive"))
    )
    (net (code "243") (name "/J800_110") (class "Default")
      (node (ref "J800") (pin "110") (pinfunction "IO_N_110") (pintype "passive"))
    )
    (net (code "244") (name "/J800_111") (class "Default")
      (node (ref "J800") (pin "111") (pinfunction "IO_N_111") (pintype "passive"))
    )
    (net (code "245") (name "/J800_112") (class "Default")
      (node (ref "J800") (pin "112") (pinfunction "IO_P_112") (pintype "passive"))
    )
    (net (code "246") (name "/J800_114") (class "Default")
      (node (ref "J800") (pin "114") (pinfunction "IO_N_114") (pintype "passive"))
    )
    (net (code "247") (name "/J800_115") (class "Default")
      (node (ref "J800") (pin "115") (pinfunction "SCLK_P_115") (pintype "passive"))
    )
    (net (code "248") (name "/J800_116") (class "Default")
      (node (ref "J800") (pin "116") (pinfunction "VIN_IO_116") (pintype "passive"))
    )
    (net (code "249") (name "/J800_117") (class "Default")
      (node (ref "J800") (pin "117") (pinfunction "SCLK_N_117") (pintype "passive"))
    )
    (net (code "250") (name "/J800_118") (class "Default")
      (node (ref "J800") (pin "118") (pinfunction "IO_P_118") (pintype "passive"))
    )
    (net (code "251") (name "/J800_119") (class "Default")
      (node (ref "J800") (pin "119") (pinfunction "IO_P_119") (pintype "passive"))
    )
    (net (code "252") (name "/J800_120") (class "Default")
      (node (ref "J800") (pin "120") (pinfunction "IO_N_120") (pintype "passive"))
    )
    (net (code "253") (name "/J800_121") (class "Default")
      (node (ref "J800") (pin "121") (pinfunction "IO_N_121") (pintype "passive"))
    )
    (net (code "254") (name "/J800_122") (class "Default")
      (node (ref "J800") (pin "122") (pinfunction "SCLK_P_122") (pintype "passive"))
    )
    (net (code "255") (name "/J800_123") (class "Default")
      (node (ref "J800") (pin "123") (pinfunction "VOUT_123") (pintype "passive"))
    )
    (net (code "256") (name "/J800_124") (class "Default")
      (node (ref "J800") (pin "124") (pinfunction "SCLK_N_124") (pintype "passive"))
    )
    (net (code "257") (name "/J800_125") (class "Default")
      (node (ref "J800") (pin "125") (pinfunction "IO_P_125") (pintype "passive"))
    )
    (net (code "258") (name "/J800_127") (class "Default")
      (node (ref "J800") (pin "127") (pinfunction "IO_N_127") (pintype "passive"))
    )
    (net (code "259") (name "/J800_128") (class "Default")
      (node (ref "J800") (pin "128") (pinfunction "IO_P_128") (pintype "passive"))
    )
    (net (code "260") (name "/J800_129") (class "Default")
      (node (ref "J800") (pin "129") (pinfunction "IO_P_129") (pintype "passive"))
    )
    (net (code "261") (name "/J800_130") (class "Default")
      (node (ref "J800") (pin "130") (pinfunction "IO_N_130") (pintype "passive"))
    )
    (net (code "262") (name "/J800_131") (class "Default")
      (node (ref "J800") (pin "131") (pinfunction "IO_N_131") (pintype "passive"))
    )
    (net (code "263") (name "/J800_132") (class "Default")
      (node (ref "J800") (pin "132") (pinfunction "IO_P_132") (pintype "passive"))
    )
    (net (code "264") (name "/J800_134") (class "Default")
      (node (ref "J800") (pin "134") (pinfunction "IO_N_134") (pintype "passive"))
    )
    (net (code "265") (name "/J800_135") (class "Default")
      (node (ref "J800") (pin "135") (pinfunction "IO_P_135") (pintype "passive"))
    )
    (net (code "266") (name "/J800_136") (class "Default")
      (node (ref "J800") (pin "136") (pinfunction "VOUT_3V3_136") (pintype "passive"))
    )
    (net (code "267") (name "/J800_137") (class "Default")
      (node (ref "J800") (pin "137") (pinfunction "IO_N_137") (pintype "passive"))
    )
    (net (code "268") (name "/J800_138") (class "Default")
      (node (ref "J800") (pin "138") (pinfunction "IO_P_138") (pintype "passive"))
    )
    (net (code "269") (name "/J800_139") (class "Default")
      (node (ref "J800") (pin "139") (pinfunction "IO_P_139") (pintype "passive"))
    )
    (net (code "270") (name "/J800_140") (class "Default")
      (node (ref "J800") (pin "140") (pinfunction "IO_N_140") (pintype "passive"))
    )
    (net (code "271") (name "/J800_141") (class "Default")
      (node (ref "J800") (pin "141") (pinfunction "IO_N_141") (pintype "passive"))
    )
    (net (code "272") (name "/J800_142") (class "Default")
      (node (ref "J800") (pin "142") (pinfunction "IO_P_142") (pintype "passive"))
    )
    (net (code "273") (name "/J800_143") (class "Default")
      (node (ref "J800") (pin "143") (pinfunction "VOUT_3V3_143") (pintype "passive"))
    )
    (net (code "274") (name "/J800_144") (class "Default")
      (node (ref "J800") (pin "144") (pinfunction "IO_N_144") (pintype "passive"))
    )
    (net (code "275") (name "/J800_145") (class "Default")
      (node (ref "J800") (pin "145") (pinfunction "IO_P_145") (pintype "passive"))
    )
    (net (code "276") (name "/J800_147") (class "Default")
      (node (ref "J800") (pin "147") (pinfunction "IO_N_147") (pintype "passive"))
    )
    (net (code "277") (name "/J800_148") (class "Default")
      (node (ref "J800") (pin "148") (pinfunction "PCLK_P_148") (pintype "passive"))
    )
    (net (code "278") (name "/J800_150") (class "Default")
      (node (ref "J800") (pin "150") (pinfunction "PCLK_N_150") (pintype "passive"))
    )
    (net (code "279") (name "/J800_151") (class "Default")
      (node (ref "J800") (pin "151") (pinfunction "SCLK_P_151") (pintype "passive"))
    )
    (net (code "280") (name "/J800_153") (class "Default")
      (node (ref "J800") (pin "153") (pinfunction "SCLK_N_153") (pintype "passive"))
    )
    (net (code "281") (name "/J800_154") (class "Default")
      (node (ref "J800") (pin "154") (pinfunction "IO_P_154") (pintype "passive"))
    )
    (net (code "282") (name "/J800_156") (class "Default")
      (node (ref "J800") (pin "156") (pinfunction "IO_N_156") (pintype "passive"))
    )
    (net (code "283") (name "/J800_157") (class "Default")
      (node (ref "J800") (pin "157") (pinfunction "IO_P_157") (pintype "passive"))
    )
    (net (code "284") (name "/J800_158") (class "Default")
      (node (ref "J800") (pin "158") (pinfunction "VIN_IO_158") (pintype "passive"))
    )
    (net (code "285") (name "/J800_159") (class "Default")
      (node (ref "J800") (pin "159") (pinfunction "IO_N_159") (pintype "passive"))
    )
    (net (code "286") (name "/J800_160") (class "Default")
      (node (ref "J800") (pin "160") (pinfunction "IO_P_160") (pintype "passive"))
    )
    (net (code "287") (name "/J800_161") (class "Default")
      (node (ref "J800") (pin "161") (pinfunction "IO_P_161") (pintype "passive"))
    )
    (net (code "288") (name "/J800_162") (class "Default")
      (node (ref "J800") (pin "162") (pinfunction "IO_N_162") (pintype "passive"))
    )
    (net (code "289") (name "/J800_163") (class "Default")
      (node (ref "J800") (pin "163") (pinfunction "IO_N_163") (pintype "passive"))
    )
    (net (code "290") (name "/J800_164") (class "Default")
      (node (ref "J800") (pin "164") (pinfunction "IO_P_164") (pintype "passive"))
    )
    (net (code "291") (name "/J800_165") (class "Default")
      (node (ref "J800") (pin "165") (pinfunction "VOUT_165") (pintype "passive"))
    )
    (net (code "292") (name "/J800_166") (class "Default")
      (node (ref "J800") (pin "166") (pinfunction "IO_N_166") (pintype "passive"))
    )
    (net (code "293") (name "/J800_167") (class "Default")
      (node (ref "J800") (pin "167") (pinfunction "RSVD_167") (pintype "passive"))
    )
    (net (code "294") (name "/JTAG_TCK") (class "Default")
      (node (ref "J700") (pin "123") (pinfunction "JTAG_TCK_123") (pintype "passive"))
    )
    (net (code "295") (name "/JTAG_TDI") (class "Default")
      (node (ref "J700") (pin "117") (pinfunction "JTAG_TDI_117") (pintype "passive"))
    )
    (net (code "296") (name "/JTAG_TDO") (class "Default")
      (node (ref "J700") (pin "121") (pinfunction "JTAG_TDO_121") (pintype "passive"))
    )
    (net (code "297") (name "/JTAG_TMS") (class "Default")
      (node (ref "J700") (pin "119") (pinfunction "JTAG_TMS_119") (pintype "passive"))
    )
    (net (code "298") (name "/MGT_CLK_1_N") (class "Default")
      (node (ref "J701") (pin "6") (pinfunction "MGT_CLK_N_6") (pintype "passive"))
    )
    (net (code "299") (name "/MGT_CLK_1_P") (class "Default")
      (node (ref "J701") (pin "4") (pinfunction "MGT_CLK_P_4") (pintype "passive"))
    )
    (net (code "300") (name "/MGT_CLK_2_N") (class "Default")
      (node (ref "J701") (pin "12") (pinfunction "MGT_CLK_N_12") (pintype "passive"))
    )
    (net (code "301") (name "/MGT_CLK_2_P") (class "Default")
      (node (ref "J701") (pin "10") (pinfunction "MGT_CLK_P_10") (pintype "passive"))
    )
    (net (code "302") (name "/MGT_RX0_N") (class "Default")
      (node (ref "J701") (pin "20") (pinfunction "MGT_RX_N_20") (pintype "passive"))
    )
    (net (code "303") (name "/MGT_RX0_P") (class "Default")
      (node (ref "J701") (pin "16") (pinfunction "MGT_RX_P_16") (pintype "passive"))
    )
    (net (code "304") (name "/MGT_RX1_N") (class "Default")
      (node (ref "J701") (pin "28") (pinfunction "MGT_RX_N_28") (pintype "passive"))
    )
    (net (code "305") (name "/MGT_RX1_P") (class "Default")
      (node (ref "J701") (pin "24") (pinfunction "MGT_RX_P_24") (pintype "passive"))
    )
    (net (code "306") (name "/MGT_RX2_N") (class "Default")
      (node (ref "J701") (pin "36") (pinfunction "MGT_RX_N_36") (pintype "passive"))
    )
    (net (code "307") (name "/MGT_RX2_P") (class "Default")
      (node (ref "J701") (pin "32") (pinfunction "MGT_RX_P_32") (pintype "passive"))
    )
    (net (code "308") (name "/MGT_RX3_N") (class "Default")
      (node (ref "J701") (pin "44") (pinfunction "MGT_RX_N_44") (pintype "passive"))
    )
    (net (code "309") (name "/MGT_RX3_P") (class "Default")
      (node (ref "J701") (pin "40") (pinfunction "MGT_RX_P_40") (pintype "passive"))
    )
    (net (code "310") (name "/MGT_TX0_N") (class "Default")
      (node (ref "J701") (pin "17") (pinfunction "MGT_TX_N_17") (pintype "passive"))
    )
    (net (code "311") (name "/MGT_TX0_P") (class "Default")
      (node (ref "J701") (pin "13") (pinfunction "MGT_TX_P_13") (pintype "passive"))
    )
    (net (code "312") (name "/MGT_TX1_N") (class "Default")
      (node (ref "J701") (pin "25") (pinfunction "MGT_TX_N_25") (pintype "passive"))
    )
    (net (code "313") (name "/MGT_TX1_P") (class "Default")
      (node (ref "J701") (pin "21") (pinfunction "MGT_TX_P_21") (pintype "passive"))
    )
    (net (code "314") (name "/MGT_TX2_N") (class "Default")
      (node (ref "J701") (pin "33") (pinfunction "MGT_TX_N_33") (pintype "passive"))
    )
    (net (code "315") (name "/MGT_TX2_P") (class "Default")
      (node (ref "J701") (pin "29") (pinfunction "MGT_TX_P_29") (pintype "passive"))
    )
    (net (code "316") (name "/MGT_TX3_N") (class "Default")
      (node (ref "J701") (pin "41") (pinfunction "MGT_TX_N_41") (pintype "passive"))
    )
    (net (code "317") (name "/MGT_TX3_P") (class "Default")
      (node (ref "J701") (pin "37") (pinfunction "MGT_TX_P_37") (pintype "passive"))
    )
    (net (code "318") (name "/SCLK{slash}MGT_RCLK_N") (class "Default")
      (node (ref "J701") (pin "5") (pinfunction "SCLK_N_5") (pintype "passive"))
    )
    (net (code "319") (name "/SCLK{slash}MGT_RCLK_P") (class "Default")
      (node (ref "J701") (pin "3") (pinfunction "SCLK_P_3") (pintype "passive"))
    )
    (net (code "320") (name "/SDO") (class "Default")
      (node (ref "J700") (pin "69") (pinfunction "IO_N_69") (pintype "passive"))
    )
    (net (code "321") (name "DGND") (class "Default")
      (node (ref "J700") (pin "108") (pinfunction "GND_108") (pintype "power_in"))
      (node (ref "J700") (pin "109") (pinfunction "GND_109") (pintype "power_in"))
      (node (ref "J700") (pin "120") (pinfunction "GND_120") (pintype "power_in"))
      (node (ref "J700") (pin "125") (pinfunction "GND_125") (pintype "power_in"))
      (node (ref "J700") (pin "13") (pinfunction "GND_13") (pintype "power_in"))
      (node (ref "J700") (pin "134") (pinfunction "GND_134") (pintype "power_in"))
      (node (ref "J700") (pin "135") (pinfunction "GND_135") (pintype "power_in"))
      (node (ref "J700") (pin "138") (pinfunction "GND_138") (pintype "power_in"))
      (node (ref "J700") (pin "139") (pinfunction "GND_139") (pintype "power_in"))
      (node (ref "J700") (pin "14") (pinfunction "GND_14") (pintype "power_in"))
      (node (ref "J700") (pin "142") (pinfunction "GND_142") (pintype "power_in"))
      (node (ref "J700") (pin "143") (pinfunction "GND_143") (pintype "power_in"))
      (node (ref "J700") (pin "166") (pinfunction "GND_166") (pintype "power_in"))
      (node (ref "J700") (pin "167") (pinfunction "GND_167") (pintype "power_in"))
      (node (ref "J700") (pin "20") (pinfunction "GND_20") (pintype "power_in"))
      (node (ref "J700") (pin "23") (pinfunction "GND_23") (pintype "power_in"))
      (node (ref "J700") (pin "32") (pinfunction "GND_32") (pintype "power_in"))
      (node (ref "J700") (pin "35") (pinfunction "GND_35") (pintype "power_in"))
      (node (ref "J700") (pin "44") (pinfunction "GND_44") (pintype "power_in"))
      (node (ref "J700") (pin "47") (pinfunction "GND_47") (pintype "power_in"))
      (node (ref "J700") (pin "56") (pinfunction "GND_56") (pintype "power_in"))
      (node (ref "J700") (pin "59") (pinfunction "GND_59") (pintype "power_in"))
      (node (ref "J700") (pin "65") (pinfunction "VOUT_65") (pintype "power_in"))
      (node (ref "J700") (pin "68") (pinfunction "GND_68") (pintype "power_in"))
      (node (ref "J700") (pin "71") (pinfunction "GND_71") (pintype "power_in"))
      (node (ref "J700") (pin "80") (pinfunction "GND_80") (pintype "power_in"))
      (node (ref "J700") (pin "83") (pinfunction "GND_83") (pintype "power_in"))
      (node (ref "J700") (pin "96") (pinfunction "GND_96") (pintype "power_in"))
      (node (ref "J700") (pin "99") (pinfunction "GND_99") (pintype "power_in"))
      (node (ref "J701") (pin "1") (pinfunction "GND_1") (pintype "passive"))
      (node (ref "J701") (pin "105") (pinfunction "GND_105") (pintype "passive"))
      (node (ref "J701") (pin "11") (pinfunction "GND_11") (pintype "passive"))
      (node (ref "J701") (pin "118") (pinfunction "GND_118") (pintype "passive"))
      (node (ref "J701") (pin "121") (pinfunction "GND_121") (pintype "passive"))
      (node (ref "J701") (pin "134") (pinfunction "GND_134") (pintype "passive"))
      (node (ref "J701") (pin "137") (pinfunction "GND_137") (pintype "passive"))
      (node (ref "J701") (pin "14") (pinfunction "GND_14") (pintype "passive"))
      (node (ref "J701") (pin "146") (pinfunction "GND_146") (pintype "passive"))
      (node (ref "J701") (pin "149") (pinfunction "GND_149") (pintype "passive"))
      (node (ref "J701") (pin "15") (pinfunction "GND_15") (pintype "passive"))
      (node (ref "J701") (pin "161") (pinfunction "GND_161") (pintype "passive"))
      (node (ref "J701") (pin "18") (pinfunction "GND_18") (pintype "passive"))
      (node (ref "J701") (pin "19") (pinfunction "GND_19") (pintype "passive"))
      (node (ref "J701") (pin "2") (pinfunction "GND_2") (pintype "passive"))
      (node (ref "J701") (pin "22") (pinfunction "GND_22") (pintype "passive"))
      (node (ref "J701") (pin "23") (pinfunction "GND_23") (pintype "passive"))
      (node (ref "J701") (pin "26") (pinfunction "GND_26") (pintype "passive"))
      (node (ref "J701") (pin "27") (pinfunction "GND_27") (pintype "passive"))
      (node (ref "J701") (pin "30") (pinfunction "GND_30") (pintype "passive"))
      (node (ref "J701") (pin "31") (pinfunction "GND_31") (pintype "passive"))
      (node (ref "J701") (pin "34") (pinfunction "GND_34") (pintype "passive"))
      (node (ref "J701") (pin "35") (pinfunction "GND_35") (pintype "passive"))
      (node (ref "J701") (pin "38") (pinfunction "GND_38") (pintype "passive"))
      (node (ref "J701") (pin "39") (pinfunction "GND_39") (pintype "passive"))
      (node (ref "J701") (pin "42") (pinfunction "GND_42") (pintype "passive"))
      (node (ref "J701") (pin "43") (pinfunction "GND_43") (pintype "passive"))
      (node (ref "J701") (pin "46") (pinfunction "GND_46") (pintype "passive"))
      (node (ref "J701") (pin "49") (pinfunction "GND_49") (pintype "passive"))
      (node (ref "J701") (pin "58") (pinfunction "GND_58") (pintype "passive"))
      (node (ref "J701") (pin "61") (pinfunction "GND_61") (pintype "passive"))
      (node (ref "J701") (pin "70") (pinfunction "GND_70") (pintype "passive"))
      (node (ref "J701") (pin "73") (pinfunction "GND_73") (pintype "passive"))
      (node (ref "J701") (pin "82") (pinfunction "GND_82") (pintype "passive"))
      (node (ref "J701") (pin "85") (pinfunction "GND_85") (pintype "passive"))
      (node (ref "J701") (pin "98") (pinfunction "GND_98") (pintype "passive"))
      (node (ref "J800") (pin "1") (pinfunction "GND_1") (pintype "passive"))
      (node (ref "J800") (pin "106") (pinfunction "GND_106") (pintype "passive"))
      (node (ref "J800") (pin "11") (pinfunction "GND_11") (pintype "passive"))
      (node (ref "J800") (pin "113") (pinfunction "GND_113") (pintype "passive"))
      (node (ref "J800") (pin "126") (pinfunction "GND_126") (pintype "passive"))
      (node (ref "J800") (pin "133") (pinfunction "GND_133") (pintype "passive"))
      (node (ref "J800") (pin "14") (pinfunction "GND_14") (pintype "passive"))
      (node (ref "J800") (pin "146") (pinfunction "GND_146") (pintype "passive"))
      (node (ref "J800") (pin "149") (pinfunction "GND_149") (pintype "passive"))
      (node (ref "J800") (pin "15") (pinfunction "GND_15") (pintype "passive"))
      (node (ref "J800") (pin "152") (pinfunction "GND_152") (pintype "passive"))
      (node (ref "J800") (pin "155") (pinfunction "GND_155") (pintype "passive"))
      (node (ref "J800") (pin "168") (pinfunction "GND_168") (pintype "passive"))
      (node (ref "J800") (pin "18") (pinfunction "GND_18") (pintype "passive"))
      (node (ref "J800") (pin "19") (pinfunction "GND_19") (pintype "passive"))
      (node (ref "J800") (pin "2") (pinfunction "GND_2") (pintype "passive"))
      (node (ref "J800") (pin "22") (pinfunction "GND_22") (pintype "passive"))
      (node (ref "J800") (pin "23") (pinfunction "GND_23") (pintype "passive"))
      (node (ref "J800") (pin "26") (pinfunction "GND_26") (pintype "passive"))
      (node (ref "J800") (pin "27") (pinfunction "GND_27") (pintype "passive"))
      (node (ref "J800") (pin "30") (pinfunction "GND_30") (pintype "passive"))
      (node (ref "J800") (pin "31") (pinfunction "GND_31") (pintype "passive"))
      (node (ref "J800") (pin "34") (pinfunction "GND_34") (pintype "passive"))
      (node (ref "J800") (pin "35") (pinfunction "GND_35") (pintype "passive"))
      (node (ref "J800") (pin "38") (pinfunction "GND_38") (pintype "passive"))
      (node (ref "J800") (pin "39") (pinfunction "GND_39") (pintype "passive"))
      (node (ref "J800") (pin "42") (pinfunction "GND_42") (pintype "passive"))
      (node (ref "J800") (pin "43") (pinfunction "GND_43") (pintype "passive"))
      (node (ref "J800") (pin "46") (pinfunction "GND_46") (pintype "passive"))
      (node (ref "J800") (pin "49") (pinfunction "GND_49") (pintype "passive"))
      (node (ref "J800") (pin "52") (pinfunction "GND_52") (pintype "passive"))
      (node (ref "J800") (pin "55") (pinfunction "GND_55") (pintype "passive"))
      (node (ref "J800") (pin "58") (pinfunction "GND_58") (pintype "passive"))
      (node (ref "J800") (pin "61") (pinfunction "GND_61") (pintype "passive"))
      (node (ref "J800") (pin "64") (pinfunction "GND_64") (pintype "passive"))
      (node (ref "J800") (pin "67") (pinfunction "GND_67") (pintype "passive"))
      (node (ref "J800") (pin "70") (pinfunction "GND_70") (pintype "passive"))
      (node (ref "J800") (pin "73") (pinfunction "GND_73") (pintype "passive"))
      (node (ref "J800") (pin "86") (pinfunction "GND_86") (pintype "passive"))
      (node (ref "J800") (pin "93") (pinfunction "GND_93") (pintype "passive"))
    )
    (net (code "322") (name "DVDD25") (class "Default")
      (node (ref "J700") (pin "38") (pinfunction "VIN_IO_38") (pintype "power_in"))
      (node (ref "J700") (pin "41") (pinfunction "VIN_IO_41") (pintype "power_in"))
      (node (ref "J700") (pin "74") (pinfunction "VIN_CFG_74") (pintype "power_in"))
      (node (ref "J700") (pin "77") (pinfunction "VIN_CFG_77") (pintype "power_in"))
      (node (ref "J701") (pin "140") (pinfunction "VIN_IO_140") (pintype "passive"))
      (node (ref "J701") (pin "143") (pinfunction "VIN_IO_143") (pintype "passive"))
      (node (ref "J701") (pin "64") (pinfunction "VIN_IO_64") (pintype "passive"))
      (node (ref "J701") (pin "67") (pinfunction "VIN_IO_67") (pintype "passive"))
      (node (ref "J701") (pin "88") (pinfunction "VIN_IO_88") (pintype "passive"))
      (node (ref "J701") (pin "95") (pinfunction "VIN_IO_95") (pintype "passive"))
    )
    (net (code "323") (name "DVDD33") (class "Default")
      (node (ref "J700") (pin "10") (pinfunction "PWR_EN_10") (pintype "passive"))
    )
    (net (code "324") (name "unconnected-(J700-BOOT_MODE-Pad126)") (class "Default")
      (node (ref "J700") (pin "126") (pinfunction "BOOT_MODE_126") (pintype "passive"))
    )
    (net (code "325") (name "unconnected-(J700-ETH_CTREF-Pad154)") (class "Default")
      (node (ref "J700") (pin "154") (pinfunction "ETH_CTREF_154") (pintype "passive"))
    )
    (net (code "326") (name "unconnected-(J700-ETH_CTREF-Pad155)") (class "Default")
      (node (ref "J700") (pin "155") (pinfunction "ETH_CTREF_155") (pintype "passive"))
    )
    (net (code "327") (name "unconnected-(J700-ETH_LED1#-Pad148)") (class "Default")
      (node (ref "J700") (pin "148") (pinfunction "ETH_LED1#_148") (pintype "passive"))
    )
    (net (code "328") (name "unconnected-(J700-ETH_LED1#-Pad149)") (class "Default")
      (node (ref "J700") (pin "149") (pinfunction "ETH_LED1#_149") (pintype "passive"))
    )
    (net (code "329") (name "unconnected-(J700-ETH_LED2#-Pad160)") (class "Default")
      (node (ref "J700") (pin "160") (pinfunction "ETH_LED2#_160") (pintype "passive"))
    )
    (net (code "330") (name "unconnected-(J700-ETH_LED2#-Pad161)") (class "Default")
      (node (ref "J700") (pin "161") (pinfunction "ETH_LED2#_161") (pintype "passive"))
    )
    (net (code "331") (name "unconnected-(J700-FLASH_CLK-Pad118)") (class "Default")
      (node (ref "J700") (pin "118") (pinfunction "FLASH_CLK_118") (pintype "passive"))
    )
    (net (code "332") (name "unconnected-(J700-FLASH_CS#-Pad116)") (class "Default")
      (node (ref "J700") (pin "116") (pinfunction "FLASH_CS#_116") (pintype "passive"))
    )
    (net (code "333") (name "unconnected-(J700-FLASH_DI-Pad114)") (class "Default")
      (node (ref "J700") (pin "114") (pinfunction "FLASH_DI_114") (pintype "passive"))
    )
    (net (code "334") (name "unconnected-(J700-FLASH_DO-Pad122)") (class "Default")
      (node (ref "J700") (pin "122") (pinfunction "FLASH_DO_122") (pintype "passive"))
    )
    (net (code "335") (name "unconnected-(J700-FPGA_DONE-Pad130)") (class "Default")
      (node (ref "J700") (pin "130") (pinfunction "FPGA_DONE_130") (pintype "passive"))
    )
    (net (code "336") (name "unconnected-(J700-ID_HDM-Pad133)") (class "Default")
      (node (ref "J700") (pin "133") (pinfunction "ID_HDM_133") (pintype "passive"))
    )
    (net (code "337") (name "unconnected-(J700-IO_N-Pad54)") (class "Default")
      (node (ref "J700") (pin "54") (pinfunction "IO_N_54") (pintype "passive"))
    )
    (net (code "338") (name "unconnected-(J700-IO_N-Pad60)") (class "Default")
      (node (ref "J700") (pin "60") (pinfunction "IO_N_60") (pintype "passive"))
    )
    (net (code "339") (name "unconnected-(J700-IO_N-Pad66)") (class "Default")
      (node (ref "J700") (pin "66") (pinfunction "IO_N_66") (pintype "passive"))
    )
    (net (code "340") (name "unconnected-(J700-IO_N-Pad84)") (class "Default")
      (node (ref "J700") (pin "84") (pinfunction "IO_N_84") (pintype "passive"))
    )
    (net (code "341") (name "unconnected-(J700-IO_P-Pad58)") (class "Default")
      (node (ref "J700") (pin "58") (pinfunction "IO_P_58") (pintype "passive"))
    )
    (net (code "342") (name "unconnected-(J700-IO_P-Pad64)") (class "Default")
      (node (ref "J700") (pin "64") (pinfunction "IO_P_64") (pintype "passive"))
    )
    (net (code "343") (name "unconnected-(J700-IO_P-Pad67)") (class "Default")
      (node (ref "J700") (pin "67") (pinfunction "IO_P_67") (pintype "passive"))
    )
    (net (code "344") (name "unconnected-(J700-IO_P-Pad82)") (class "Default")
      (node (ref "J700") (pin "82") (pinfunction "IO_P_82") (pintype "passive"))
    )
    (net (code "345") (name "unconnected-(J700-IO_P-Pad92)") (class "Default")
      (node (ref "J700") (pin "92") (pinfunction "IO_P_92") (pintype "passive"))
    )
    (net (code "346") (name "unconnected-(J700-PCLK_N-Pad87)") (class "Default")
      (node (ref "J700") (pin "87") (pinfunction "PCLK_N_87") (pintype "passive"))
    )
    (net (code "347") (name "unconnected-(J700-PCLK_P-Pad85)") (class "Default")
      (node (ref "J700") (pin "85") (pinfunction "PCLK_P_85") (pintype "passive"))
    )
    (net (code "348") (name "unconnected-(J700-POR#_LOAD#-Pad132)") (class "Default")
      (node (ref "J700") (pin "132") (pinfunction "POR#_LOAD#_132") (pintype "passive"))
    )
    (net (code "349") (name "unconnected-(J700-PWR_GOOD-Pad12)") (class "Default")
      (node (ref "J700") (pin "12") (pinfunction "PWR_GOOD_12") (pintype "passive"))
    )
    (net (code "350") (name "unconnected-(J700-RSVD-Pad110)") (class "Default")
      (node (ref "J700") (pin "110") (pinfunction "RSVD_110") (pintype "passive"))
    )
    (net (code "351") (name "unconnected-(J700-RSVD-Pad112)") (class "Default")
      (node (ref "J700") (pin "112") (pinfunction "RSVD_112") (pintype "passive"))
    )
    (net (code "352") (name "unconnected-(J700-SRST#_RDY#-Pad124)") (class "Default")
      (node (ref "J700") (pin "124") (pinfunction "SRST#_RDY#_124") (pintype "passive"))
    )
    (net (code "353") (name "unconnected-(J700-USB_CPEN-Pad128)") (class "Default")
      (node (ref "J700") (pin "128") (pinfunction "USB_CPEN_128") (pintype "passive"))
    )
    (net (code "354") (name "unconnected-(J700-USB_DM-Pad129)") (class "Default")
      (node (ref "J700") (pin "129") (pinfunction "USB_DM_129") (pintype "passive"))
    )
    (net (code "355") (name "unconnected-(J700-USB_DP-Pad127)") (class "Default")
      (node (ref "J700") (pin "127") (pinfunction "USB_DP_127") (pintype "passive"))
    )
    (net (code "356") (name "unconnected-(J700-USB_SSRX_N-Pad141)") (class "Default")
      (node (ref "J700") (pin "141") (pinfunction "USB_SSRX_N_141") (pintype "passive"))
    )
    (net (code "357") (name "unconnected-(J700-USB_SSRX_P-Pad137)") (class "Default")
      (node (ref "J700") (pin "137") (pinfunction "USB_SSRX_P_137") (pintype "passive"))
    )
    (net (code "358") (name "unconnected-(J700-USB_SSTX_N-Pad140)") (class "Default")
      (node (ref "J700") (pin "140") (pinfunction "USB_SSTX_N_140") (pintype "passive"))
    )
    (net (code "359") (name "unconnected-(J700-USB_SSTX_P-Pad136)") (class "Default")
      (node (ref "J700") (pin "136") (pinfunction "USB_SSTX_P_136") (pintype "passive"))
    )
    (net (code "360") (name "unconnected-(J700-VBUS_HDP-Pad131)") (class "Default")
      (node (ref "J700") (pin "131") (pinfunction "VBUS_HDP_131") (pintype "passive"))
    )
    (net (code "361") (name "unconnected-(J700-VIN_BAT-Pad168)") (class "Default")
      (node (ref "J700") (pin "168") (pinfunction "VIN_BAT_168") (pintype "power_in"))
    )
    (net (code "362") (name "unconnected-(J700-VMON-Pad102)") (class "Default")
      (node (ref "J700") (pin "102") (pinfunction "VMON_102") (pintype "passive"))
    )
    (net (code "363") (name "unconnected-(J700-VOUT-Pad53)") (class "Default")
      (node (ref "J700") (pin "53") (pinfunction "VOUT_53") (pintype "power_in"))
    )
    (net (code "364") (name "unconnected-(J700-VOUT-Pad62)") (class "Default")
      (node (ref "J700") (pin "62") (pinfunction "VOUT_62") (pintype "power_in"))
    )
    (net (code "365") (name "unconnected-(J700-VOUT-Pad89)") (class "Default")
      (node (ref "J700") (pin "89") (pinfunction "VOUT_89") (pintype "power_in"))
    )
    (net (code "366") (name "unconnected-(J700-VOUT_3V3-Pad26)") (class "Default")
      (node (ref "J700") (pin "26") (pinfunction "VOUT_3V3_26") (pintype "power_in"))
    )
    (net (code "367") (name "unconnected-(J700-VOUT_3V3-Pad29)") (class "Default")
      (node (ref "J700") (pin "29") (pinfunction "VOUT_3V3_29") (pintype "power_in"))
    )
    (net (code "368") (name "unconnected-(J700-VOUT_3V3-Pad86)") (class "Default")
      (node (ref "J700") (pin "86") (pinfunction "VOUT_3V3_86") (pintype "power_in"))
    )
    (net (code "369") (name "unconnected-(J701-GND-Pad158)") (class "Default")
      (node (ref "J701") (pin "158") (pinfunction "GND_158") (pintype "passive"))
    )
    (net (code "370") (name "unconnected-(J701-VMON-Pad8)") (class "Default")
      (node (ref "J701") (pin "8") (pinfunction "VMON_8") (pintype "passive"))
    )
    (net (code "371") (name "unconnected-(J701-VMON-Pad167)") (class "Default")
      (node (ref "J701") (pin "167") (pinfunction "VMON_167") (pintype "passive"))
    )
    (net (code "372") (name "unconnected-(J701-VMON-Pad168)") (class "Default")
      (node (ref "J701") (pin "168") (pinfunction "VMON_168") (pintype "passive"))
    )
    (net (code "373") (name "unconnected-(J701-VOUT-Pad52)") (class "Default")
      (node (ref "J701") (pin "52") (pinfunction "VOUT_52") (pintype "passive"))
    )
    (net (code "374") (name "unconnected-(J701-VOUT-Pad76)") (class "Default")
      (node (ref "J701") (pin "76") (pinfunction "VOUT_76") (pintype "passive"))
    )
    (net (code "375") (name "unconnected-(J701-VOUT-Pad108)") (class "Default")
      (node (ref "J701") (pin "108") (pinfunction "VOUT_108") (pintype "passive"))
    )
    (net (code "376") (name "unconnected-(J701-VOUT-Pad128)") (class "Default")
      (node (ref "J701") (pin "128") (pinfunction "VOUT_128") (pintype "passive"))
    )
    (net (code "377") (name "unconnected-(J701-VOUT_3V3-Pad55)") (class "Default")
      (node (ref "J701") (pin "55") (pinfunction "VOUT_3V3_55") (pintype "passive"))
    )
    (net (code "378") (name "unconnected-(J701-VOUT_3V3-Pad79)") (class "Default")
      (node (ref "J701") (pin "79") (pinfunction "VOUT_3V3_79") (pintype "passive"))
    )
    (net (code "379") (name "unconnected-(J701-VOUT_3V3-Pad115)") (class "Default")
      (node (ref "J701") (pin "115") (pinfunction "VOUT_3V3_115") (pintype "passive"))
    )
    (net (code "380") (name "unconnected-(J701-VOUT_3V3-Pad127)") (class "Default")
      (node (ref "J701") (pin "127") (pinfunction "VOUT_3V3_127") (pintype "passive"))
    )
    (net (code "381") (name "unconnected-(J701-VOUT_3V3-Pad152)") (class "Default")
      (node (ref "J701") (pin "152") (pinfunction "VOUT_3V3_152") (pintype "passive"))
    )
    (net (code "382") (name "unconnected-(J701-VOUT_3V3-Pad155)") (class "Default")
      (node (ref "J701") (pin "155") (pinfunction "VOUT_3V3_155") (pintype "passive"))
    )
  )
)
